# IO.net
KiCad netlist of a schematic drawn in Altium Designer
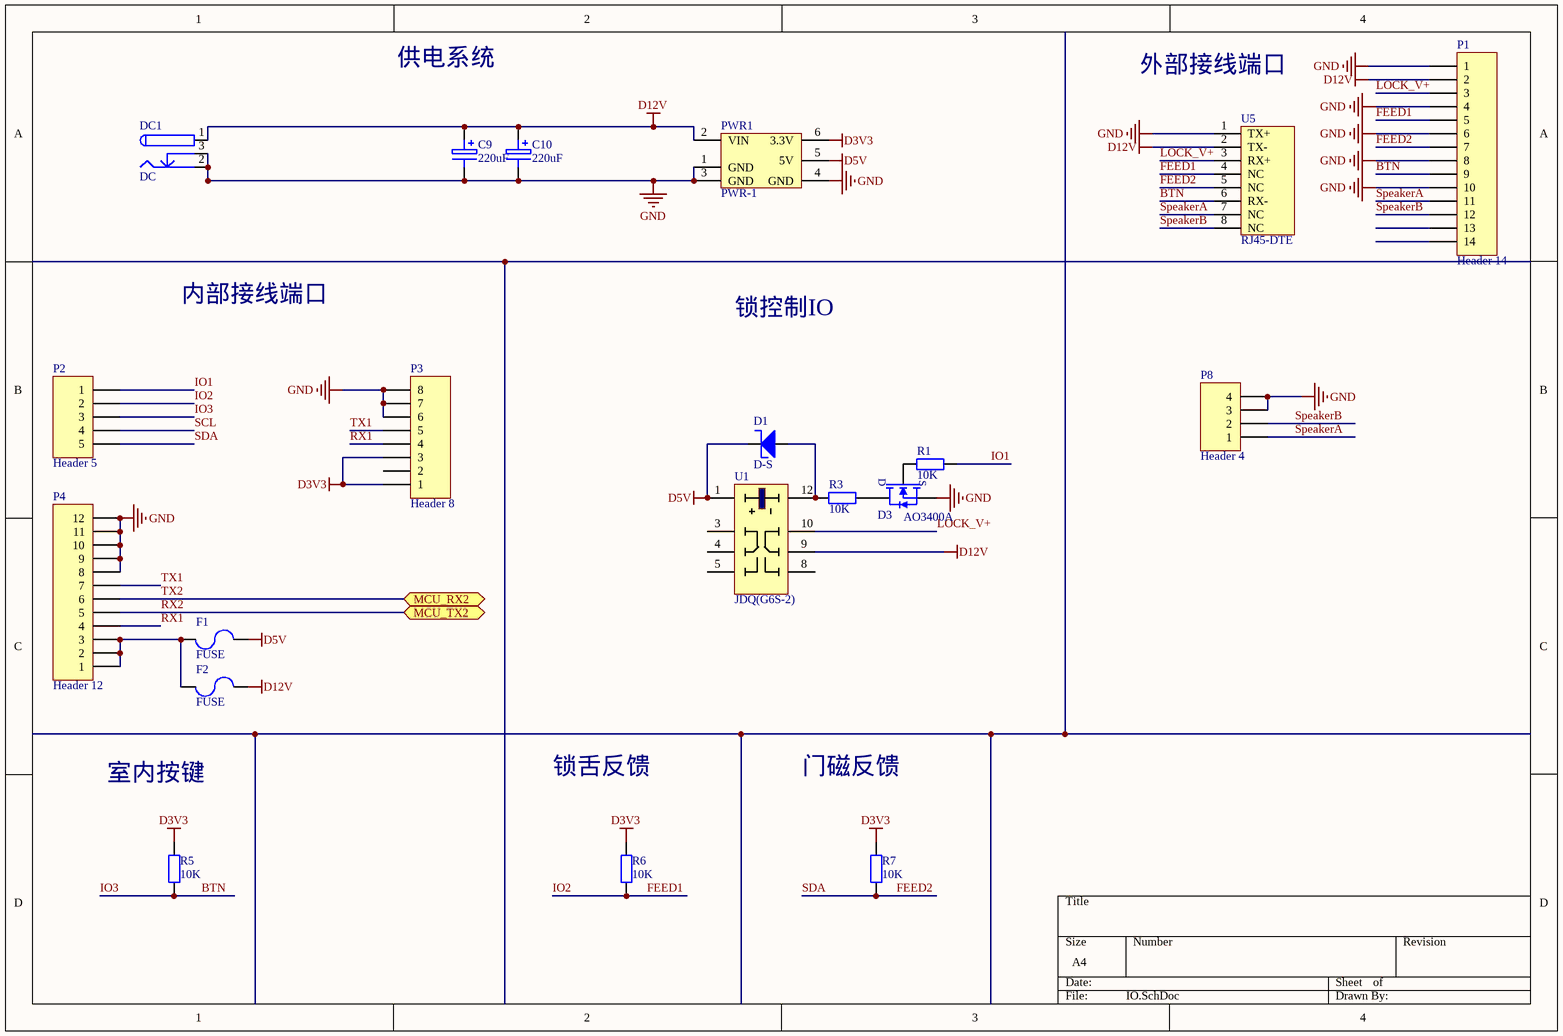
[diagram p0: IO.SchDoc]

(export (version "E")
  (design (tool "Eeschema 10.0.6"))
  (components
    (comp (ref "C9")
      (value "220uF")
      (footprint "RB.2/.4")
      (description "电解电容")
      (libsource (lib "lib_AD") (part "CAP-E"))
    )
    (comp (ref "C10")
      (value "220uF")
      (footprint "RB.2/.4")
      (description "电解电容")
      (libsource (lib "lib_AD") (part "CAP-E"))
    )
    (comp (ref "D1")
      (value "D-S")
      (footprint "DO-214AC(SMA)")
      (description "肖特基二极管")
      (libsource (lib "lib_AD") (part "D-S"))
    )
    (comp (ref "D3")
      (value "AO3400A")
      (footprint "SOT23A")
      (description "NMOS")
      (libsource (lib "lib_AD") (part "MOS-N"))
    )
    (comp (ref "DC1")
      (value "DC")
      (footprint "DC005")
      (description "圆形电源接口")
      (libsource (lib "lib_AD") (part "DC00X"))
    )
    (comp (ref "F1")
      (value "FUSE")
      (footprint "0805F")
      (description "CR-1812-050A60V")
      (libsource (lib "lib_AD") (part "FUSE"))
    )
    (comp (ref "F2")
      (value "FUSE")
      (footprint "0805F")
      (description "CR-1812-050A60V")
      (libsource (lib "lib_AD") (part "FUSE"))
    )
    (comp (ref "P1")
      (value "Header 14")
      (footprint "KF128-5.08-14")
      (description "Header, 14-Pin")
      (fields (field (name "PUBLISHER") "Altium Limited"))
      (libsource (lib "lib_AD") (part "Header 14"))
    )
    (comp (ref "P2")
      (value "Header 5")
      (footprint "XH2.54-5")
      (description "Header, 5-Pin")
      (fields (field (name "PUBLISHER") "Altium Limited"))
      (libsource (lib "lib_AD") (part "Header 5"))
    )
    (comp (ref "P3")
      (value "Header 8")
      (footprint "FPC/1.25T-6P")
      (description "Header, 8-Pin")
      (fields (field (name "PUBLISHER") "Altium Limited"))
      (libsource (lib "lib_AD") (part "Header 8"))
    )
    (comp (ref "P4")
      (value "Header 12")
      (footprint "FFC/SM1.0-2H10")
      (description "Header, 12-Pin")
      (fields (field (name "PUBLISHER") "Altium Limited"))
      (libsource (lib "lib_AD") (part "Header 12"))
    )
    (comp (ref "P8")
      (value "Header 4")
      (footprint "FPC/1.25T-2P")
      (description "Header, 4-Pin")
      (fields (field (name "PUBLISHER") "Altium Limited"))
      (libsource (lib "lib_AD") (part "Header 4"))
    )
    (comp (ref "PWR1") (value "PWR-1") (footprint "PWR-1") (libsource (lib "lib_AD") (part "PWR-1")))
    (comp (ref "R1")
      (value "10K")
      (footprint "0603R")
      (description "普通电阻")
      (libsource (lib "lib_AD") (part "RES"))
    )
    (comp (ref "R3")
      (value "10K")
      (footprint "0603R")
      (description "普通电阻")
      (libsource (lib "lib_AD") (part "RES"))
    )
    (comp (ref "R5")
      (value "10K")
      (footprint "0603R")
      (description "普通电阻")
      (libsource (lib "") (part "RES_1"))
    )
    (comp (ref "R6")
      (value "10K")
      (footprint "0603R")
      (description "普通电阻")
      (libsource (lib "") (part "RES_1"))
    )
    (comp (ref "R7")
      (value "10K")
      (footprint "0603R")
      (description "普通电阻")
      (libsource (lib "") (part "RES_1"))
    )
    (comp (ref "U1")
      (value "JDQ(G6S-2)")
      (footprint "JDQ-G6S-2")
      (description "继电器（G6S-2 5VDC）")
      (libsource (lib "lib_AD") (part "JDQ(G6S-2)"))
    )
    (comp (ref "U5") (value "RJ45-DTE") (footprint "RJ45") (libsource (lib "lib_AD") (part "RJ45-DTE")))
  )
  (nets
    (net (code "1") (name "/BTN") (class "Default")
      (node (ref "P1") (pin "9") (pinfunction "9_9") (pintype "passive"))
      (node (ref "P2") (pin "3") (pinfunction "3_3") (pintype "passive"))
      (node (ref "R5") (pin "1") (pinfunction "1_1") (pintype "passive"))
      (node (ref "U5") (pin "6") (pinfunction "RX-_6") (pintype "passive"))
    )
    (net (code "2") (name "/FEED1") (class "Default")
      (node (ref "P1") (pin "5") (pinfunction "5_5") (pintype "passive"))
      (node (ref "P2") (pin "2") (pinfunction "2_2") (pintype "passive"))
      (node (ref "R6") (pin "1") (pinfunction "1_1") (pintype "passive"))
      (node (ref "U5") (pin "4") (pinfunction "NC_4") (pintype "passive"))
    )
    (net (code "3") (name "/FEED2") (class "Default")
      (node (ref "P1") (pin "7") (pinfunction "7_7") (pintype "passive"))
      (node (ref "P2") (pin "5") (pinfunction "5_5") (pintype "passive"))
      (node (ref "R7") (pin "1") (pinfunction "1_1") (pintype "passive"))
      (node (ref "U5") (pin "5") (pinfunction "NC_5") (pintype "passive"))
    )
    (net (code "4") (name "/IO1") (class "Default")
      (node (ref "P2") (pin "1") (pinfunction "1_1") (pintype "passive"))
      (node (ref "R1") (pin "2") (pinfunction "2_2") (pintype "passive"))
    )
    (net (code "5") (name "/LOCK_V+") (class "Default")
      (node (ref "P1") (pin "3") (pinfunction "3_3") (pintype "passive"))
      (node (ref "U1") (pin "10") (pinfunction "10_10") (pintype "passive"))
      (node (ref "U5") (pin "3") (pinfunction "RX+_3") (pintype "passive"))
    )
    (net (code "6") (name "/RX1") (class "Default")
      (node (ref "P3") (pin "4") (pinfunction "4_4") (pintype "passive"))
      (node (ref "P4") (pin "4") (pinfunction "4_4") (pintype "passive"))
    )
    (net (code "7") (name "/RX2") (class "Default")
      (node (ref "P4") (pin "5") (pinfunction "5_5") (pintype "passive"))
    )
    (net (code "8") (name "/SCL") (class "Default")
      (node (ref "P2") (pin "4") (pinfunction "4_4") (pintype "passive"))
    )
    (net (code "9") (name "/SpeakerA") (class "Default")
      (node (ref "P1") (pin "11") (pinfunction "11_11") (pintype "passive"))
      (node (ref "P8") (pin "1") (pinfunction "1_1") (pintype "passive"))
      (node (ref "U5") (pin "7") (pinfunction "NC_7") (pintype "passive"))
    )
    (net (code "10") (name "/SpeakerB") (class "Default")
      (node (ref "P1") (pin "12") (pinfunction "12_12") (pintype "passive"))
      (node (ref "P8") (pin "2") (pinfunction "2_2") (pintype "passive"))
      (node (ref "U5") (pin "8") (pinfunction "NC_8") (pintype "passive"))
    )
    (net (code "11") (name "/TX1") (class "Default")
      (node (ref "P3") (pin "5") (pinfunction "5_5") (pintype "passive"))
      (node (ref "P4") (pin "7") (pinfunction "7_7") (pintype "passive"))
    )
    (net (code "12") (name "/TX2") (class "Default")
      (node (ref "P4") (pin "6") (pinfunction "6_6") (pintype "passive"))
    )
    (net (code "13") (name "D3V3") (class "Default")
      (node (ref "P3") (pin "1") (pinfunction "1_1") (pintype "passive"))
      (node (ref "P3") (pin "3") (pinfunction "3_3") (pintype "passive"))
      (node (ref "PWR1") (pin "6") (pinfunction "3.3V_6") (pintype "passive"))
      (node (ref "R5") (pin "2") (pinfunction "2_2") (pintype "passive"))
      (node (ref "R6") (pin "2") (pinfunction "2_2") (pintype "passive"))
      (node (ref "R7") (pin "2") (pinfunction "2_2") (pintype "passive"))
    )
    (net (code "14") (name "D5V") (class "Default")
      (node (ref "D1") (pin "K") (pinfunction "2_K") (pintype "passive"))
      (node (ref "F1") (pin "1") (pinfunction "1_1") (pintype "passive"))
      (node (ref "PWR1") (pin "5") (pinfunction "5V_5") (pintype "passive"))
      (node (ref "U1") (pin "1") (pinfunction "1_1") (pintype "passive"))
    )
    (net (code "15") (name "D12V") (class "Default")
      (node (ref "C10") (pin "1") (pinfunction "1_1") (pintype "passive"))
      (node (ref "C9") (pin "1") (pinfunction "1_1") (pintype "passive"))
      (node (ref "DC1") (pin "1") (pinfunction "1_1") (pintype "power_in"))
      (node (ref "F2") (pin "1") (pinfunction "1_1") (pintype "passive"))
      (node (ref "P1") (pin "2") (pinfunction "2_2") (pintype "passive"))
      (node (ref "PWR1") (pin "2") (pinfunction "VIN_2") (pintype "passive"))
      (node (ref "U1") (pin "9") (pinfunction "9_9") (pintype "passive"))
      (node (ref "U5") (pin "2") (pinfunction "TX-_2") (pintype "passive"))
    )
    (net (code "16") (name "GND") (class "Default")
      (node (ref "C10") (pin "2") (pinfunction "2_2") (pintype "passive"))
      (node (ref "C9") (pin "2") (pinfunction "2_2") (pintype "passive"))
      (node (ref "D3") (pin "2") (pinfunction "S_2") (pintype "passive"))
      (node (ref "DC1") (pin "2") (pinfunction "2_2") (pintype "power_in"))
      (node (ref "DC1") (pin "3") (pinfunction "3_3") (pintype "power_in"))
      (node (ref "P1") (pin "1") (pinfunction "1_1") (pintype "passive"))
      (node (ref "P1") (pin "10") (pinfunction "10_10") (pintype "passive"))
      (node (ref "P1") (pin "4") (pinfunction "4_4") (pintype "passive"))
      (node (ref "P1") (pin "6") (pinfunction "6_6") (pintype "passive"))
      (node (ref "P1") (pin "8") (pinfunction "8_8") (pintype "passive"))
      (node (ref "P3") (pin "6") (pinfunction "6_6") (pintype "passive"))
      (node (ref "P3") (pin "7") (pinfunction "7_7") (pintype "passive"))
      (node (ref "P3") (pin "8") (pinfunction "8_8") (pintype "passive"))
      (node (ref "P4") (pin "10") (pinfunction "10_10") (pintype "passive"))
      (node (ref "P4") (pin "11") (pinfunction "11_11") (pintype "passive"))
      (node (ref "P4") (pin "12") (pinfunction "12_12") (pintype "passive"))
      (node (ref "P4") (pin "8") (pinfunction "8_8") (pintype "passive"))
      (node (ref "P4") (pin "9") (pinfunction "9_9") (pintype "passive"))
      (node (ref "P8") (pin "3") (pinfunction "3_3") (pintype "passive"))
      (node (ref "P8") (pin "4") (pinfunction "4_4") (pintype "passive"))
      (node (ref "PWR1") (pin "1") (pinfunction "GND_1") (pintype "passive"))
      (node (ref "PWR1") (pin "3") (pinfunction "GND_3") (pintype "passive"))
      (node (ref "PWR1") (pin "4") (pinfunction "GND_4") (pintype "passive"))
      (node (ref "U5") (pin "1") (pinfunction "TX+_1") (pintype "passive"))
    )
    (net (code "17") (name "Net-(D1-1)") (class "Default")
      (node (ref "D1") (pin "A") (pinfunction "1_A") (pintype "passive"))
      (node (ref "R3") (pin "1") (pinfunction "1_1") (pintype "passive"))
      (node (ref "U1") (pin "12") (pinfunction "12_12") (pintype "passive"))
    )
    (net (code "18") (name "Net-(D3-D)") (class "Default")
      (node (ref "D3") (pin "3") (pinfunction "D_3") (pintype "passive"))
      (node (ref "R3") (pin "2") (pinfunction "2_2") (pintype "passive"))
    )
    (net (code "19") (name "Net-(D3-G)") (class "Default")
      (node (ref "D3") (pin "1") (pinfunction "G_1") (pintype "passive"))
      (node (ref "R1") (pin "1") (pinfunction "1_1") (pintype "passive"))
    )
    (net (code "20") (name "Net-(F1-Pad2)") (class "Default")
      (node (ref "F1") (pin "2") (pinfunction "2_2") (pintype "passive"))
      (node (ref "F2") (pin "2") (pinfunction "2_2") (pintype "passive"))
      (node (ref "P4") (pin "1") (pinfunction "1_1") (pintype "passive"))
      (node (ref "P4") (pin "2") (pinfunction "2_2") (pintype "passive"))
      (node (ref "P4") (pin "3") (pinfunction "3_3") (pintype "passive"))
    )
    (net (code "21") (name "unconnected-(P1-Pad13)") (class "Default")
      (node (ref "P1") (pin "13") (pinfunction "13_13") (pintype "passive"))
    )
    (net (code "22") (name "unconnected-(P1-Pad14)") (class "Default")
      (node (ref "P1") (pin "14") (pinfunction "14_14") (pintype "passive"))
    )
    (net (code "23") (name "unconnected-(P3-Pad2)") (class "Default")
      (node (ref "P3") (pin "2") (pinfunction "2_2") (pintype "passive"))
    )
    (net (code "24") (name "unconnected-(U1-Pad3)") (class "Default")
      (node (ref "U1") (pin "3") (pinfunction "3_3") (pintype "passive"))
    )
    (net (code "25") (name "unconnected-(U1-Pad4)") (class "Default")
      (node (ref "U1") (pin "4") (pinfunction "4_4") (pintype "passive"))
    )
    (net (code "26") (name "unconnected-(U1-Pad5)") (class "Default")
      (node (ref "U1") (pin "5") (pinfunction "5_5") (pintype "passive"))
    )
    (net (code "27") (name "unconnected-(U1-Pad8)") (class "Default")
      (node (ref "U1") (pin "8") (pinfunction "8_8") (pintype "passive"))
    )
  )
)
